# primary_cap_int.net
KiCad netlist of a schematic drawn in Altium Designer
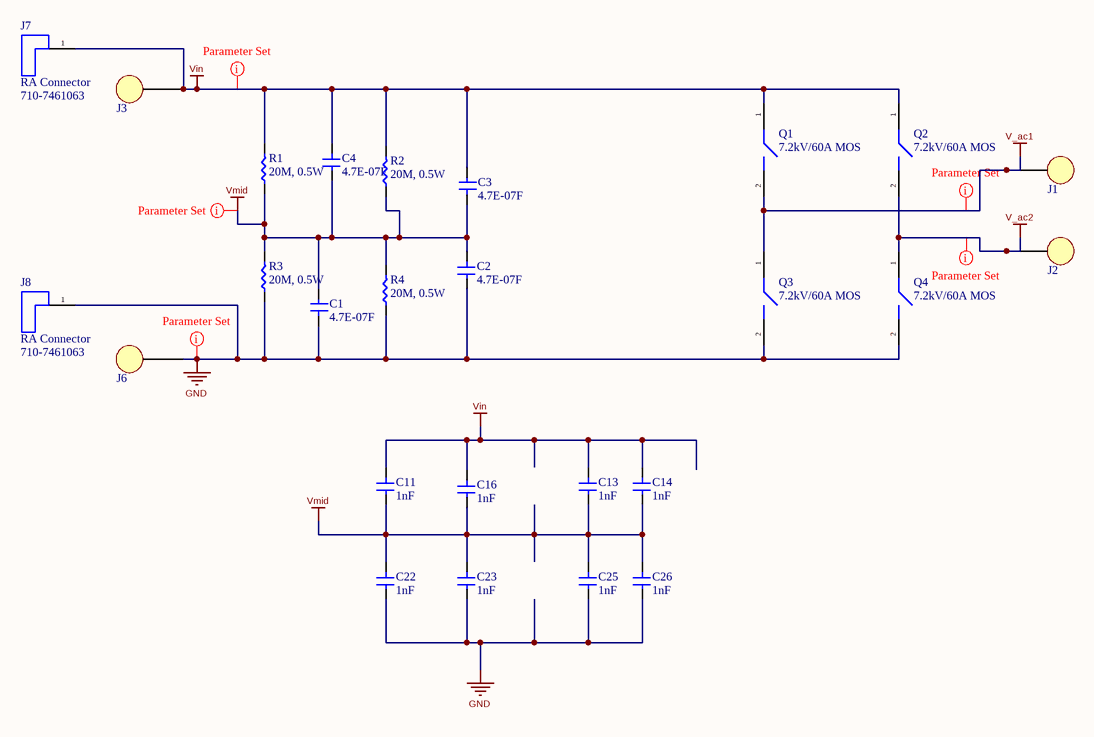
[diagram p0: primary_cap_int.SchDoc]

(export (version "E")
  (design (tool "Eeschema 10.0.6"))
  (components
    (comp (ref "C1")
      (value "4.7E-07F")
      (footprint "C4BSYBX3470ZBMJ")
      (description "Cap, 0.47UF, 750VAC, Film, Radial")
      (fields
        (field (name "MANUFACTURER") "KEMET")
        (field (name "MANUFACTURER PART NUMBER") "C4BSYBX3470ZBMJ")
      )
      (libsource (lib "primary_cap") (part "C4BSYBX3470ZBMJ"))
    )
    (comp (ref "C2")
      (value "4.7E-07F")
      (footprint "C4BSYBX3470ZBMJ")
      (description "Cap, 0.47UF, 750VAC, Film, Radial")
      (fields
        (field (name "MANUFACTURER") "KEMET")
        (field (name "MANUFACTURER PART NUMBER") "C4BSYBX3470ZBMJ")
      )
      (libsource (lib "primary_cap") (part "C4BSYBX3470ZBMJ"))
    )
    (comp (ref "C3")
      (value "4.7E-07F")
      (footprint "C4BSYBX3470ZBMJ")
      (description "Cap, 0.47UF, 750VAC, Film, Radial")
      (fields
        (field (name "MANUFACTURER") "KEMET")
        (field (name "MANUFACTURER PART NUMBER") "C4BSYBX3470ZBMJ")
      )
      (libsource (lib "primary_cap") (part "C4BSYBX3470ZBMJ"))
    )
    (comp (ref "C4")
      (value "4.7E-07F")
      (footprint "C4BSYBX3470ZBMJ")
      (description "Cap, 0.47UF, 750VAC, Film, Radial")
      (fields
        (field (name "MANUFACTURER") "KEMET")
        (field (name "MANUFACTURER PART NUMBER") "C4BSYBX3470ZBMJ")
      )
      (libsource (lib "primary_cap") (part "C4BSYBX3470ZBMJ"))
    )
    (comp (ref "C11")
      (value "1nF")
      (footprint "PHE450XB4100JB04R17")
      (description "CAP FILM 1000PF 5% 3KVDC RADIAL")
      (fields
        (field (name "MANUFACTURER") "KEMET")
        (field (name "MANUFACTURER PART NUMBER") "PHE450XB4100JB04R17")
      )
      (libsource (lib "primary_cap") (part "PHE450XB4100JB04R17"))
    )
    (comp (ref "C13")
      (value "1nF")
      (footprint "PHE450XB4100JB04R17")
      (description "CAP FILM 1000PF 5% 3KVDC RADIAL")
      (fields
        (field (name "MANUFACTURER") "KEMET")
        (field (name "MANUFACTURER PART NUMBER") "PHE450XB4100JB04R17")
      )
      (libsource (lib "primary_cap") (part "PHE450XB4100JB04R17"))
    )
    (comp (ref "C14")
      (value "1nF")
      (footprint "PHE450XB4100JB04R17")
      (description "CAP FILM 1000PF 5% 3KVDC RADIAL")
      (fields
        (field (name "MANUFACTURER") "KEMET")
        (field (name "MANUFACTURER PART NUMBER") "PHE450XB4100JB04R17")
      )
      (libsource (lib "primary_cap") (part "PHE450XB4100JB04R17"))
    )
    (comp (ref "C16")
      (value "1nF")
      (footprint "PHE450XB4100JB04R17")
      (description "CAP FILM 1000PF 5% 3KVDC RADIAL")
      (fields
        (field (name "MANUFACTURER") "KEMET")
        (field (name "MANUFACTURER PART NUMBER") "PHE450XB4100JB04R17")
      )
      (libsource (lib "primary_cap") (part "PHE450XB4100JB04R17"))
    )
    (comp (ref "C22")
      (value "1nF")
      (footprint "PHE450XB4100JB04R17")
      (description "CAP FILM 1000PF 5% 3KVDC RADIAL")
      (fields
        (field (name "MANUFACTURER") "KEMET")
        (field (name "MANUFACTURER PART NUMBER") "PHE450XB4100JB04R17")
      )
      (libsource (lib "primary_cap") (part "PHE450XB4100JB04R17"))
    )
    (comp (ref "C23")
      (value "1nF")
      (footprint "PHE450XB4100JB04R17")
      (description "CAP FILM 1000PF 5% 3KVDC RADIAL")
      (fields
        (field (name "MANUFACTURER") "KEMET")
        (field (name "MANUFACTURER PART NUMBER") "PHE450XB4100JB04R17")
      )
      (libsource (lib "primary_cap") (part "PHE450XB4100JB04R17"))
    )
    (comp (ref "C25")
      (value "1nF")
      (footprint "PHE450XB4100JB04R17")
      (description "CAP FILM 1000PF 5% 3KVDC RADIAL")
      (fields
        (field (name "MANUFACTURER") "KEMET")
        (field (name "MANUFACTURER PART NUMBER") "PHE450XB4100JB04R17")
      )
      (libsource (lib "primary_cap") (part "PHE450XB4100JB04R17"))
    )
    (comp (ref "C26")
      (value "1nF")
      (footprint "PHE450XB4100JB04R17")
      (description "CAP FILM 1000PF 5% 3KVDC RADIAL")
      (fields
        (field (name "MANUFACTURER") "KEMET")
        (field (name "MANUFACTURER PART NUMBER") "PHE450XB4100JB04R17")
      )
      (libsource (lib "primary_cap") (part "PHE450XB4100JB04R17"))
    )
    (comp (ref "J1")
      (value "TERM PCB SNAP-IN VERT HD M5 THRD")
      (footprint "M4_9pin_shank")
      (fields
        (field (name "MANUFACTURER") "Keystone Electronics")
        (field (name "MANUFACTURER PART NUMBER") "7807")
      )
      (libsource (lib "diodebridge") (part "7807"))
    )
    (comp (ref "J2")
      (value "TERM PCB SNAP-IN VERT HD M5 THRD")
      (footprint "M4_9pin_shank")
      (fields
        (field (name "MANUFACTURER") "Keystone Electronics")
        (field (name "MANUFACTURER PART NUMBER") "7807")
      )
      (libsource (lib "diodebridge") (part "7807"))
    )
    (comp (ref "J3")
      (value "TERM PCB SNAP-IN VERT HD M5 THRD")
      (footprint "M4_9pin_shank")
      (fields
        (field (name "MANUFACTURER") "Keystone Electronics")
        (field (name "MANUFACTURER PART NUMBER") "7807")
      )
      (libsource (lib "diodebridge") (part "7807"))
    )
    (comp (ref "J6")
      (value "TERM PCB SNAP-IN VERT HD M5 THRD")
      (footprint "M4_9pin_shank")
      (fields
        (field (name "MANUFACTURER") "Keystone Electronics")
        (field (name "MANUFACTURER PART NUMBER") "7807")
      )
      (libsource (lib "diodebridge") (part "7807"))
    )
    (comp (ref "J7")
      (value "RA Connector")
      (footprint "7461063")
      (description "TERM PWR ELEMENT M4 8 PIN PCB RA")
      (fields
        (field (name "MANUFACTURER") "Wurth Electronics")
        (field (name "MANUFACTURER PART NUMBER") "7461063")
        (field (name "SUPPLIER PART NUMBER 1") "710-7461063")
      )
      (libsource (lib "primary_cap") (part "7461063"))
    )
    (comp (ref "J8")
      (value "RA Connector")
      (footprint "7461063")
      (description "TERM PWR ELEMENT M4 8 PIN PCB RA")
      (fields
        (field (name "MANUFACTURER") "Wurth Electronics")
        (field (name "MANUFACTURER PART NUMBER") "7461063")
        (field (name "SUPPLIER PART NUMBER 1") "710-7461063")
      )
      (libsource (lib "primary_cap") (part "7461063"))
    )
    (comp (ref "Q1")
      (value "7.2kV/60A MOS")
      (footprint "Austin Supermos_r1")
      (libsource (lib "primary_cap") (part "Austin SuperMos"))
    )
    (comp (ref "Q2")
      (value "7.2kV/60A MOS")
      (footprint "Austin Supermos_r1")
      (libsource (lib "primary_cap") (part "Austin SuperMos"))
    )
    (comp (ref "Q3")
      (value "7.2kV/60A MOS")
      (footprint "Austin Supermos_r1")
      (libsource (lib "primary_cap") (part "Austin SuperMos"))
    )
    (comp (ref "Q4")
      (value "7.2kV/60A MOS")
      (footprint "Austin Supermos_r1")
      (libsource (lib "primary_cap") (part "Austin SuperMos"))
    )
    (comp (ref "R1")
      (value "20M, 0.5W")
      (footprint "VR37000002005JR500")
      (description "RES 20M OHM 1/2W 5% AXIAL")
      (fields
        (field (name "MANUFACTURER") "Vishay BCcomponents")
        (field (name "MANUFACTURER PART NUMBER") "VR37000002005JR500")
      )
      (libsource (lib "primary_cap") (part "VR37000002005JR500"))
    )
    (comp (ref "R2")
      (value "20M, 0.5W")
      (footprint "VR37000002005JR500")
      (description "RES 20M OHM 1/2W 5% AXIAL")
      (fields
        (field (name "MANUFACTURER") "Vishay BCcomponents")
        (field (name "MANUFACTURER PART NUMBER") "VR37000002005JR500")
      )
      (libsource (lib "primary_cap") (part "VR37000002005JR500"))
    )
    (comp (ref "R3")
      (value "20M, 0.5W")
      (footprint "VR37000002005JR500")
      (description "RES 20M OHM 1/2W 5% AXIAL")
      (fields
        (field (name "MANUFACTURER") "Vishay BCcomponents")
        (field (name "MANUFACTURER PART NUMBER") "VR37000002005JR500")
      )
      (libsource (lib "primary_cap") (part "VR37000002005JR500"))
    )
    (comp (ref "R4")
      (value "20M, 0.5W")
      (footprint "VR37000002005JR500")
      (description "RES 20M OHM 1/2W 5% AXIAL")
      (fields
        (field (name "MANUFACTURER") "Vishay BCcomponents")
        (field (name "MANUFACTURER PART NUMBER") "VR37000002005JR500")
      )
      (libsource (lib "primary_cap") (part "VR37000002005JR500"))
    )
  )
  (nets
    (net (code "1") (name "GND") (class "Default")
      (node (ref "C1") (pin "2") (pinfunction "2_2") (pintype "passive"))
      (node (ref "C2") (pin "1") (pinfunction "1_1") (pintype "passive"))
      (node (ref "C22") (pin "1") (pinfunction "1_1") (pintype "passive"))
      (node (ref "C23") (pin "1") (pinfunction "1_1") (pintype "passive"))
      (node (ref "C25") (pin "1") (pinfunction "1_1") (pintype "passive"))
      (node (ref "C26") (pin "1") (pinfunction "1_1") (pintype "passive"))
      (node (ref "J6") (pin "1") (pinfunction "1_1") (pintype "passive"))
      (node (ref "J8") (pin "1") (pinfunction "1_1") (pintype "power_in"))
      (node (ref "Q3") (pin "2") (pinfunction "2_2") (pintype "power_in"))
      (node (ref "Q4") (pin "2") (pinfunction "2_2") (pintype "power_in"))
      (node (ref "R3") (pin "1") (pinfunction "3_1") (pintype "passive"))
      (node (ref "R4") (pin "1") (pinfunction "3_1") (pintype "passive"))
    )
    (net (code "2") (name "V_ac1") (class "Default")
      (node (ref "J1") (pin "1") (pinfunction "1_1") (pintype "passive"))
      (node (ref "Q1") (pin "2") (pinfunction "2_2") (pintype "power_in"))
      (node (ref "Q3") (pin "1") (pinfunction "1_1") (pintype "power_in"))
    )
    (net (code "3") (name "V_ac2") (class "Default")
      (node (ref "J2") (pin "1") (pinfunction "1_1") (pintype "passive"))
      (node (ref "Q2") (pin "2") (pinfunction "2_2") (pintype "power_in"))
      (node (ref "Q4") (pin "1") (pinfunction "1_1") (pintype "power_in"))
    )
    (net (code "4") (name "Vin") (class "Default")
      (node (ref "C11") (pin "2") (pinfunction "2_2") (pintype "passive"))
      (node (ref "C13") (pin "2") (pinfunction "2_2") (pintype "passive"))
      (node (ref "C14") (pin "2") (pinfunction "2_2") (pintype "passive"))
      (node (ref "C16") (pin "2") (pinfunction "2_2") (pintype "passive"))
      (node (ref "C3") (pin "1") (pinfunction "1_1") (pintype "passive"))
      (node (ref "C4") (pin "2") (pinfunction "2_2") (pintype "passive"))
      (node (ref "J3") (pin "1") (pinfunction "1_1") (pintype "passive"))
      (node (ref "J7") (pin "1") (pinfunction "1_1") (pintype "power_in"))
      (node (ref "Q1") (pin "1") (pinfunction "1_1") (pintype "power_in"))
      (node (ref "Q2") (pin "1") (pinfunction "1_1") (pintype "power_in"))
      (node (ref "R1") (pin "2") (pinfunction "4_2") (pintype "passive"))
      (node (ref "R2") (pin "2") (pinfunction "4_2") (pintype "passive"))
    )
    (net (code "5") (name "Vmid") (class "Default")
      (node (ref "C1") (pin "1") (pinfunction "1_1") (pintype "passive"))
      (node (ref "C11") (pin "1") (pinfunction "1_1") (pintype "passive"))
      (node (ref "C13") (pin "1") (pinfunction "1_1") (pintype "passive"))
      (node (ref "C14") (pin "1") (pinfunction "1_1") (pintype "passive"))
      (node (ref "C16") (pin "1") (pinfunction "1_1") (pintype "passive"))
      (node (ref "C2") (pin "2") (pinfunction "2_2") (pintype "passive"))
      (node (ref "C22") (pin "2") (pinfunction "2_2") (pintype "passive"))
      (node (ref "C23") (pin "2") (pinfunction "2_2") (pintype "passive"))
      (node (ref "C25") (pin "2") (pinfunction "2_2") (pintype "passive"))
      (node (ref "C26") (pin "2") (pinfunction "2_2") (pintype "passive"))
      (node (ref "C3") (pin "2") (pinfunction "2_2") (pintype "passive"))
      (node (ref "C4") (pin "1") (pinfunction "1_1") (pintype "passive"))
      (node (ref "R1") (pin "1") (pinfunction "3_1") (pintype "passive"))
      (node (ref "R2") (pin "1") (pinfunction "3_1") (pintype "passive"))
      (node (ref "R3") (pin "2") (pinfunction "4_2") (pintype "passive"))
      (node (ref "R4") (pin "2") (pinfunction "4_2") (pintype "passive"))
    )
  )
)
